# MCU.net
KiCad netlist of a schematic drawn in Altium Designer
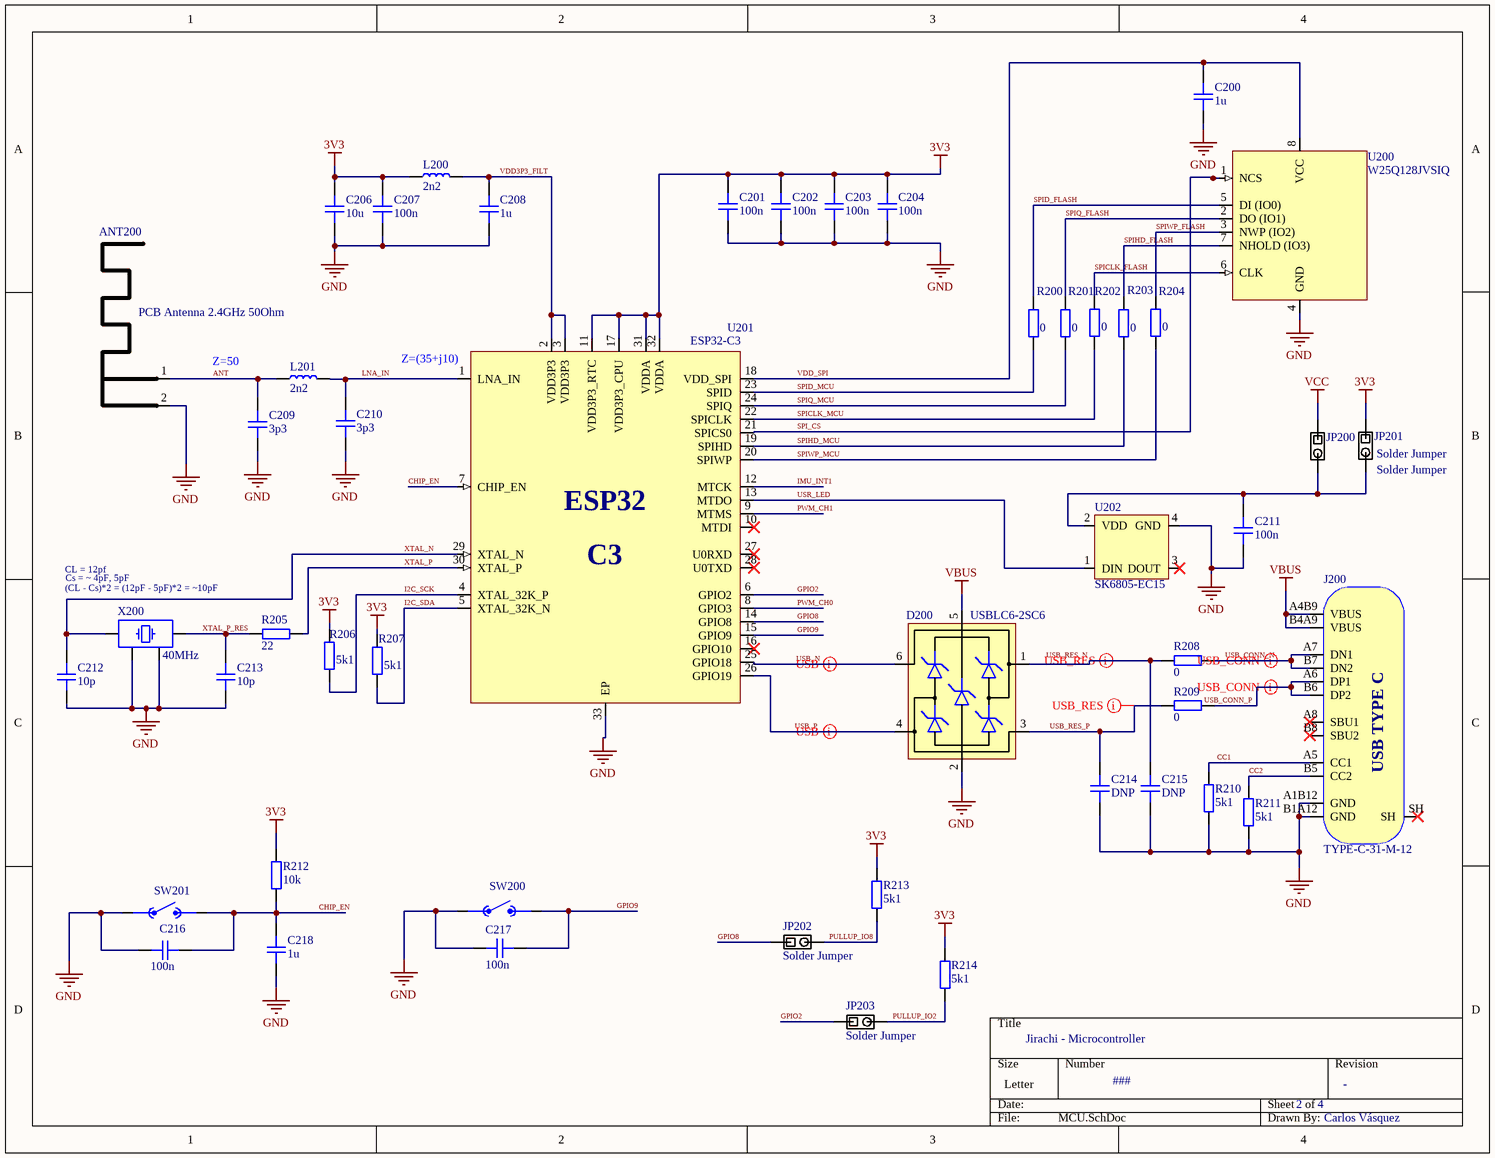
[diagram p0: MCU.SchDoc]

(export (version "E")
  (design (tool "Eeschema 10.0.6"))
  (components
    (comp (ref "ANT200")
      (value "PCB Antenna 2.4GHz 50Ohm")
      (footprint "ANT_IFA_USB_2_4GHZ_50R")
      (description "Inverted F 2.4GHz ISM PCB Antenna 50 Ohm")
      (libsource (lib "Schematic-Lib-PhilsLab") (part "ANT_IFA_USB_2_4GHZ_50R"))
    )
    (comp (ref "C200")
      (value "1u")
      (footprint "CAP_0402")
      (description "Capacitor SMD 0402")
      (libsource (lib "Schematic-Lib-PhilsLab") (part "CAP_0402"))
    )
    (comp (ref "C201")
      (value "100n")
      (footprint "CAP_0402")
      (description "Capacitor SMD 0402")
      (libsource (lib "Schematic-Lib-PhilsLab") (part "CAP_0402"))
    )
    (comp (ref "C202")
      (value "100n")
      (footprint "CAP_0402")
      (description "Capacitor SMD 0402")
      (libsource (lib "Schematic-Lib-PhilsLab") (part "CAP_0402"))
    )
    (comp (ref "C203")
      (value "100n")
      (footprint "CAP_0402")
      (description "Capacitor SMD 0402")
      (libsource (lib "Schematic-Lib-PhilsLab") (part "CAP_0402"))
    )
    (comp (ref "C204")
      (value "100n")
      (footprint "CAP_0402")
      (description "Capacitor SMD 0402")
      (libsource (lib "Schematic-Lib-PhilsLab") (part "CAP_0402"))
    )
    (comp (ref "C206")
      (value "10u")
      (footprint "CAP_0603")
      (description "Capacitor SMD 0603")
      (libsource (lib "Schematic-Lib-PhilsLab") (part "CAP_0603"))
    )
    (comp (ref "C207")
      (value "100n")
      (footprint "CAP_0402")
      (description "Capacitor SMD 0402")
      (libsource (lib "Schematic-Lib-PhilsLab") (part "CAP_0402"))
    )
    (comp (ref "C208")
      (value "1u")
      (footprint "CAP_0402")
      (description "Capacitor SMD 0402")
      (libsource (lib "Schematic-Lib-PhilsLab") (part "CAP_0402"))
    )
    (comp (ref "C209")
      (value "3p3")
      (footprint "CAP_0402")
      (description "Capacitor SMD 0402")
      (libsource (lib "Schematic-Lib-PhilsLab") (part "CAP_0402"))
    )
    (comp (ref "C210")
      (value "3p3")
      (footprint "CAP_0402")
      (description "Capacitor SMD 0402")
      (libsource (lib "Schematic-Lib-PhilsLab") (part "CAP_0402"))
    )
    (comp (ref "C211")
      (value "100n")
      (footprint "CAP_0402")
      (description "Capacitor SMD 0402")
      (libsource (lib "Schematic-Lib-PhilsLab") (part "CAP_0402"))
    )
    (comp (ref "C212")
      (value "10p")
      (footprint "CAP_0402")
      (description "Capacitor SMD 0402")
      (libsource (lib "Schematic-Lib-PhilsLab") (part "CAP_0402"))
    )
    (comp (ref "C213")
      (value "10p")
      (footprint "CAP_0402")
      (description "Capacitor SMD 0402")
      (libsource (lib "Schematic-Lib-PhilsLab") (part "CAP_0402"))
    )
    (comp (ref "C214")
      (value "DNP")
      (footprint "CAP_0603")
      (description "Capacitor SMD 0603")
      (libsource (lib "Schematic-Lib-PhilsLab") (part "CAP_0603"))
    )
    (comp (ref "C215")
      (value "DNP")
      (footprint "CAP_0603")
      (description "Capacitor SMD 0603")
      (libsource (lib "Schematic-Lib-PhilsLab") (part "CAP_0603"))
    )
    (comp (ref "C216")
      (value "100n")
      (footprint "CAP_0402")
      (description "Capacitor SMD 0402")
      (libsource (lib "Schematic-Lib-PhilsLab") (part "CAP_0402"))
    )
    (comp (ref "C217")
      (value "100n")
      (footprint "CAP_0402")
      (description "Capacitor SMD 0402")
      (libsource (lib "Schematic-Lib-PhilsLab") (part "CAP_0402"))
    )
    (comp (ref "C218")
      (value "1u")
      (footprint "CAP_0402")
      (description "Capacitor SMD 0402")
      (libsource (lib "Schematic-Lib-PhilsLab") (part "CAP_0402"))
    )
    (comp (ref "D200")
      (value "USBLC6-2SC6")
      (footprint "SOT-23-6")
      (description "Low-Capacitance ESD Protection USB")
      (fields (field (name "MANUFACTURER") "STMicroelectronics"))
      (libsource (lib "Schematic-Lib-PhilsLab") (part "USBLC6-2SC6"))
    )
    (comp (ref "J200")
      (value "TYPE-C-31-M-12")
      (footprint "TYPE-C-31-M-12")
      (description "USB Type C Connector Horizontal SMT")
      (fields (field (name "MANUFACTURER") "Koren Hroparts"))
      (libsource (lib "Schematic-Lib-PhilsLab") (part "TYPE-C-31-M-12"))
    )
    (comp (ref "JP200")
      (value "Solder Jumper")
      (footprint "SolderJumper_Single")
      (description "Solder Jumper Single 0.5mm Pitch")
      (libsource (lib "Schematic-Lib-PhilsLab") (part "SolderJumper_Single"))
    )
    (comp (ref "JP201")
      (value "Solder Jumper")
      (footprint "SolderJumper_Single")
      (description "Solder Jumper Single 0.5mm Pitch")
      (libsource (lib "Schematic-Lib-PhilsLab") (part "SolderJumper_Single"))
    )
    (comp (ref "JP202")
      (value "Solder Jumper")
      (footprint "SolderJumper_Single")
      (description "Solder Jumper Single 0.5mm Pitch")
      (libsource (lib "Schematic-Lib-PhilsLab") (part "SolderJumper_Single"))
    )
    (comp (ref "JP203")
      (value "Solder Jumper")
      (footprint "SolderJumper_Single")
      (description "Solder Jumper Single 0.5mm Pitch")
      (libsource (lib "Schematic-Lib-PhilsLab") (part "SolderJumper_Single"))
    )
    (comp (ref "L200")
      (value "2n2")
      (footprint "IND_0402")
      (description "Inductor SMD 0402")
      (libsource (lib "Schematic-Lib-PhilsLab") (part "IND_0402"))
    )
    (comp (ref "L201")
      (value "2n2")
      (footprint "IND_0402")
      (description "Inductor SMD 0402")
      (libsource (lib "Schematic-Lib-PhilsLab") (part "IND_0402"))
    )
    (comp (ref "R200")
      (value "0")
      (footprint "RES_0402")
      (description "Resistor SMD 0402")
      (libsource (lib "Schematic-Lib-PhilsLab") (part "RES_0402"))
    )
    (comp (ref "R201")
      (value "0")
      (footprint "RES_0402")
      (description "Resistor SMD 0402")
      (libsource (lib "Schematic-Lib-PhilsLab") (part "RES_0402"))
    )
    (comp (ref "R202")
      (value "0")
      (footprint "RES_0402")
      (description "Resistor SMD 0402")
      (libsource (lib "Schematic-Lib-PhilsLab") (part "RES_0402"))
    )
    (comp (ref "R203")
      (value "0")
      (footprint "RES_0402")
      (description "Resistor SMD 0402")
      (libsource (lib "Schematic-Lib-PhilsLab") (part "RES_0402"))
    )
    (comp (ref "R204")
      (value "0")
      (footprint "RES_0402")
      (description "Resistor SMD 0402")
      (libsource (lib "Schematic-Lib-PhilsLab") (part "RES_0402"))
    )
    (comp (ref "R205")
      (value "22")
      (footprint "RES_0402")
      (description "Resistor SMD 0402")
      (libsource (lib "Schematic-Lib-PhilsLab") (part "RES_0402"))
    )
    (comp (ref "R206")
      (value "5k1")
      (footprint "RES_0402")
      (description "Resistor SMD 0402")
      (libsource (lib "Schematic-Lib-PhilsLab") (part "RES_0402"))
    )
    (comp (ref "R207")
      (value "5k1")
      (footprint "RES_0402")
      (description "Resistor SMD 0402")
      (libsource (lib "Schematic-Lib-PhilsLab") (part "RES_0402"))
    )
    (comp (ref "R208")
      (value "0")
      (footprint "RES_0402")
      (description "Resistor SMD 0402")
      (libsource (lib "Schematic-Lib-PhilsLab") (part "RES_0402"))
    )
    (comp (ref "R209")
      (value "0")
      (footprint "RES_0402")
      (description "Resistor SMD 0402")
      (libsource (lib "Schematic-Lib-PhilsLab") (part "RES_0402"))
    )
    (comp (ref "R210")
      (value "5k1")
      (footprint "RES_0402")
      (description "Resistor SMD 0402")
      (libsource (lib "Schematic-Lib-PhilsLab") (part "RES_0402"))
    )
    (comp (ref "R211")
      (value "5k1")
      (footprint "RES_0402")
      (description "Resistor SMD 0402")
      (libsource (lib "Schematic-Lib-PhilsLab") (part "RES_0402"))
    )
    (comp (ref "R212")
      (value "10k")
      (footprint "RES_0402")
      (description "Resistor SMD 0402")
      (libsource (lib "Schematic-Lib-PhilsLab") (part "RES_0402"))
    )
    (comp (ref "R213")
      (value "5k1")
      (footprint "RES_0402")
      (description "Resistor SMD 0402")
      (libsource (lib "Schematic-Lib-PhilsLab") (part "RES_0402"))
    )
    (comp (ref "R214")
      (value "5k1")
      (footprint "RES_0402")
      (description "Resistor SMD 0402")
      (libsource (lib "Schematic-Lib-PhilsLab") (part "RES_0402"))
    )
    (comp (ref "SW200")
      (value "SW SPST SMD Terreneitor")
      (footprint "SW SPST SMD Terreneitor")
      (description "SPST SW TS-1187A-B-A-B")
      (libsource (lib "TerreneitorLib") (part "SW SPST SMD Terreneitor"))
    )
    (comp (ref "SW201")
      (value "SW SPST SMD Terreneitor")
      (footprint "SW SPST SMD Terreneitor")
      (description "SPST SW TS-1187A-B-A-B")
      (libsource (lib "TerreneitorLib") (part "SW SPST SMD Terreneitor"))
    )
    (comp (ref "U200")
      (value "W25Q128JVSIQ")
      (footprint "SOIC8_208 mil")
      (description "128M-BIT\r\nSERIAL FLASH MEMORY WITH\r\nDUAL/QUAD SPI & QPI & DTR SOIC-8 208 MIL")
      (fields
        (field (name "MANUFACTURER") "Winbond")
        (field (name "MANUFACTURER PART NUMBER") "W25Q128JVSIM")
      )
      (libsource (lib "Schematic-Lib-PhilsLab") (part "W25Q128JVSIQ"))
    )
    (comp (ref "U201")
      (value "ESP32-C3")
      (footprint "QFN32-5x5")
      (fields (field (name "MANUFACTURER") "Espressif"))
      (libsource (lib "Schematic-Lib-PhilsLab") (part "ESP32-C3"))
    )
    (comp (ref "U202")
      (value "SK6805-EC15")
      (footprint "SK6805-EC15")
      (libsource (lib "TerreneitorLib") (part "SK6805-EC15"))
    )
    (comp (ref "X200")
      (value "40MHz")
      (footprint "XTAL_3225")
      (description "Crystal SMD 40MHz 10PPM 12pF 3225")
      (fields
        (field (name "MANUFACTURER") "Epson")
        (field (name "MANUFACTURER PART NUMBER") "TSX-3225 24.0000MF15X-AC")
      )
      (libsource (lib "Schematic-Lib-PhilsLab") (part "TSX-3225_24.0000MF15X-AC"))
    )
  )
  (nets
    (net (code "1") (name "/ANT") (class "Default")
      (node (ref "ANT200") (pin "1") (pinfunction "RF_1") (pintype "passive"))
      (node (ref "C209") (pin "2") (pinfunction "2_2") (pintype "passive"))
      (node (ref "L201") (pin "1") (pinfunction "1_1") (pintype "passive"))
    )
    (net (code "2") (name "/CC1") (class "Default")
      (node (ref "J200") (pin "A5") (pinfunction "CC1_A5") (pintype "passive"))
      (node (ref "R210") (pin "2") (pinfunction "2_2") (pintype "passive"))
    )
    (net (code "3") (name "/CC2") (class "Default")
      (node (ref "J200") (pin "B5") (pinfunction "CC2_B5") (pintype "tri_state"))
      (node (ref "R211") (pin "2") (pinfunction "2_2") (pintype "passive"))
    )
    (net (code "4") (name "/CHIP_EN") (class "Default")
      (node (ref "C216") (pin "1") (pinfunction "1_1") (pintype "passive"))
      (node (ref "C218") (pin "2") (pinfunction "2_2") (pintype "passive"))
      (node (ref "R212") (pin "1") (pinfunction "1_1") (pintype "passive"))
      (node (ref "SW201") (pin "2") (pinfunction "2_2") (pintype "passive"))
      (node (ref "U201") (pin "7") (pinfunction "CHIP_EN_7") (pintype "input"))
    )
    (net (code "5") (name "/GPIO2") (class "Default")
      (node (ref "JP203") (pin "1") (pinfunction "1_1") (pintype "passive"))
      (node (ref "U201") (pin "6") (pinfunction "GPIO2_6") (pintype "bidirectional"))
    )
    (net (code "6") (name "/GPIO8") (class "Default")
      (node (ref "JP202") (pin "1") (pinfunction "1_1") (pintype "passive"))
      (node (ref "U201") (pin "14") (pinfunction "GPIO8_14") (pintype "bidirectional"))
    )
    (net (code "7") (name "/GPIO9") (class "Default")
      (node (ref "C217") (pin "1") (pinfunction "1_1") (pintype "passive"))
      (node (ref "SW200") (pin "2") (pinfunction "2_2") (pintype "passive"))
      (node (ref "U201") (pin "15") (pinfunction "GPIO9_15") (pintype "bidirectional"))
    )
    (net (code "8") (name "/I2C_SCK") (class "Default")
      (node (ref "R206") (pin "1") (pinfunction "1_1") (pintype "passive"))
      (node (ref "U201") (pin "4") (pinfunction "XTAL_32K_P_4") (pintype "bidirectional"))
    )
    (net (code "9") (name "/I2C_SDA") (class "Default")
      (node (ref "R207") (pin "1") (pinfunction "1_1") (pintype "passive"))
      (node (ref "U201") (pin "5") (pinfunction "XTAL_32K_N_5") (pintype "bidirectional"))
    )
    (net (code "10") (name "/IMU_INT1") (class "Default")
      (node (ref "U201") (pin "12") (pinfunction "MTCK_12") (pintype "bidirectional"))
    )
    (net (code "11") (name "/LNA_IN") (class "Default")
      (node (ref "C210") (pin "2") (pinfunction "2_2") (pintype "passive"))
      (node (ref "L201") (pin "2") (pinfunction "2_2") (pintype "passive"))
      (node (ref "U201") (pin "1") (pinfunction "LNA_IN_1") (pintype "bidirectional"))
    )
    (net (code "12") (name "/PULLUP_IO2") (class "Default")
      (node (ref "JP203") (pin "2") (pinfunction "2_2") (pintype "passive"))
      (node (ref "R214") (pin "1") (pinfunction "1_1") (pintype "passive"))
    )
    (net (code "13") (name "/PULLUP_IO8") (class "Default")
      (node (ref "JP202") (pin "2") (pinfunction "2_2") (pintype "passive"))
      (node (ref "R213") (pin "1") (pinfunction "1_1") (pintype "passive"))
    )
    (net (code "14") (name "/PWM_CH0") (class "Default")
      (node (ref "U201") (pin "8") (pinfunction "GPIO3_8") (pintype "bidirectional"))
    )
    (net (code "15") (name "/PWM_CH1") (class "Default")
      (node (ref "U201") (pin "9") (pinfunction "MTMS_9") (pintype "bidirectional"))
    )
    (net (code "16") (name "/SPICLK_FLASH") (class "Default")
      (node (ref "R202") (pin "2") (pinfunction "2_2") (pintype "passive"))
      (node (ref "U200") (pin "6") (pinfunction "CLK_6") (pintype "input"))
    )
    (net (code "17") (name "/SPICLK_MCU") (class "Default")
      (node (ref "R202") (pin "1") (pinfunction "1_1") (pintype "passive"))
      (node (ref "U201") (pin "22") (pinfunction "SPICLK_22") (pintype "bidirectional"))
    )
    (net (code "18") (name "/SPID_FLASH") (class "Default")
      (node (ref "R200") (pin "2") (pinfunction "2_2") (pintype "passive"))
      (node (ref "U200") (pin "5") (pinfunction "DI_(IO0)_5") (pintype "bidirectional"))
    )
    (net (code "19") (name "/SPID_MCU") (class "Default")
      (node (ref "R200") (pin "1") (pinfunction "1_1") (pintype "passive"))
      (node (ref "U201") (pin "23") (pinfunction "SPID_23") (pintype "bidirectional"))
    )
    (net (code "20") (name "/SPIHD_FLASH") (class "Default")
      (node (ref "R203") (pin "2") (pinfunction "2_2") (pintype "passive"))
      (node (ref "U200") (pin "7") (pinfunction "NHOLD_(IO3)_7") (pintype "bidirectional"))
    )
    (net (code "21") (name "/SPIHD_MCU") (class "Default")
      (node (ref "R203") (pin "1") (pinfunction "1_1") (pintype "passive"))
      (node (ref "U201") (pin "19") (pinfunction "SPIHD_19") (pintype "bidirectional"))
    )
    (net (code "22") (name "/SPIQ_FLASH") (class "Default")
      (node (ref "R201") (pin "2") (pinfunction "2_2") (pintype "passive"))
      (node (ref "U200") (pin "2") (pinfunction "DO_(IO1)_2") (pintype "bidirectional"))
    )
    (net (code "23") (name "/SPIQ_MCU") (class "Default")
      (node (ref "R201") (pin "1") (pinfunction "1_1") (pintype "passive"))
      (node (ref "U201") (pin "24") (pinfunction "SPIQ_24") (pintype "bidirectional"))
    )
    (net (code "24") (name "/SPIWP_FLASH") (class "Default")
      (node (ref "R204") (pin "2") (pinfunction "2_2") (pintype "passive"))
      (node (ref "U200") (pin "3") (pinfunction "NWP_(IO2)_3") (pintype "bidirectional"))
    )
    (net (code "25") (name "/SPIWP_MCU") (class "Default")
      (node (ref "R204") (pin "1") (pinfunction "1_1") (pintype "passive"))
      (node (ref "U201") (pin "20") (pinfunction "SPIWP_20") (pintype "bidirectional"))
    )
    (net (code "26") (name "/SPI_CS") (class "Default")
      (node (ref "U200") (pin "1") (pinfunction "NCS_1") (pintype "input"))
      (node (ref "U201") (pin "21") (pinfunction "SPICS0_21") (pintype "bidirectional"))
    )
    (net (code "27") (name "/USB_CONN_N") (class "Default")
      (node (ref "J200") (pin "A7") (pinfunction "DN1_A7") (pintype "bidirectional"))
      (node (ref "J200") (pin "B7") (pinfunction "DN2_B7") (pintype "bidirectional"))
      (node (ref "R208") (pin "2") (pinfunction "2_2") (pintype "passive"))
    )
    (net (code "28") (name "/USB_CONN_P") (class "Default")
      (node (ref "J200") (pin "A6") (pinfunction "DP1_A6") (pintype "bidirectional"))
      (node (ref "J200") (pin "B6") (pinfunction "DP2_B6") (pintype "bidirectional"))
      (node (ref "R209") (pin "2") (pinfunction "2_2") (pintype "passive"))
    )
    (net (code "29") (name "/USB_N") (class "Default")
      (node (ref "D200") (pin "6") (pinfunction "IO1_6") (pintype "bidirectional"))
      (node (ref "U201") (pin "25") (pinfunction "GPIO18_25") (pintype "bidirectional"))
    )
    (net (code "30") (name "/USB_P") (class "Default")
      (node (ref "D200") (pin "4") (pinfunction "IO2_4") (pintype "bidirectional"))
      (node (ref "U201") (pin "26") (pinfunction "GPIO19_26") (pintype "bidirectional"))
    )
    (net (code "31") (name "/USB_RES_N") (class "Default")
      (node (ref "C215") (pin "2") (pinfunction "2_2") (pintype "passive"))
      (node (ref "D200") (pin "1") (pinfunction "IO1_1") (pintype "bidirectional"))
      (node (ref "R208") (pin "1") (pinfunction "1_1") (pintype "passive"))
    )
    (net (code "32") (name "/USB_RES_P") (class "Default")
      (node (ref "C214") (pin "2") (pinfunction "2_2") (pintype "passive"))
      (node (ref "D200") (pin "3") (pinfunction "IO2_3") (pintype "bidirectional"))
      (node (ref "R209") (pin "1") (pinfunction "1_1") (pintype "passive"))
    )
    (net (code "33") (name "/USR_LED") (class "Default")
      (node (ref "U201") (pin "13") (pinfunction "MTDO_13") (pintype "bidirectional"))
      (node (ref "U202") (pin "1") (pinfunction "DIN_1") (pintype "passive"))
    )
    (net (code "34") (name "/VDD3P3_FILT") (class "Default")
      (node (ref "C208") (pin "2") (pinfunction "2_2") (pintype "passive"))
      (node (ref "L200") (pin "2") (pinfunction "2_2") (pintype "passive"))
      (node (ref "U201") (pin "2") (pinfunction "VDD3P3_2") (pintype "power_in"))
      (node (ref "U201") (pin "3") (pinfunction "VDD3P3_3") (pintype "power_in"))
    )
    (net (code "35") (name "/VDD_SPI") (class "Default")
      (node (ref "C200") (pin "2") (pinfunction "2_2") (pintype "passive"))
      (node (ref "U200") (pin "8") (pinfunction "VCC_8") (pintype "power_in"))
      (node (ref "U201") (pin "18") (pinfunction "VDD_SPI_18") (pintype "power_in"))
    )
    (net (code "36") (name "/XTAL_N") (class "Default")
      (node (ref "C212") (pin "1") (pinfunction "1_1") (pintype "passive"))
      (node (ref "U201") (pin "29") (pinfunction "XTAL_N_29") (pintype "input"))
      (node (ref "X200") (pin "1") (pinfunction "1_1") (pintype "passive"))
    )
    (net (code "37") (name "/XTAL_P") (class "Default")
      (node (ref "R205") (pin "2") (pinfunction "2_2") (pintype "passive"))
      (node (ref "U201") (pin "30") (pinfunction "XTAL_P_30") (pintype "input"))
    )
    (net (code "38") (name "/XTAL_P_RES") (class "Default")
      (node (ref "C213") (pin "1") (pinfunction "1_1") (pintype "passive"))
      (node (ref "R205") (pin "1") (pinfunction "1_1") (pintype "passive"))
      (node (ref "X200") (pin "3") (pinfunction "3_3") (pintype "passive"))
    )
    (net (code "39") (name "3V3") (class "Default")
      (node (ref "C201") (pin "1") (pinfunction "1_1") (pintype "passive"))
      (node (ref "C202") (pin "1") (pinfunction "1_1") (pintype "passive"))
      (node (ref "C203") (pin "1") (pinfunction "1_1") (pintype "passive"))
      (node (ref "C204") (pin "1") (pinfunction "1_1") (pintype "passive"))
      (node (ref "C206") (pin "1") (pinfunction "1_1") (pintype "passive"))
      (node (ref "C207") (pin "1") (pinfunction "1_1") (pintype "passive"))
      (node (ref "JP201") (pin "1") (pinfunction "1_1") (pintype "passive"))
      (node (ref "L200") (pin "1") (pinfunction "1_1") (pintype "passive"))
      (node (ref "R206") (pin "2") (pinfunction "2_2") (pintype "passive"))
      (node (ref "R207") (pin "2") (pinfunction "2_2") (pintype "passive"))
      (node (ref "R212") (pin "2") (pinfunction "2_2") (pintype "passive"))
      (node (ref "R213") (pin "2") (pinfunction "2_2") (pintype "passive"))
      (node (ref "R214") (pin "2") (pinfunction "2_2") (pintype "passive"))
      (node (ref "U201") (pin "11") (pinfunction "VDD3P3_RTC_11") (pintype "power_in"))
      (node (ref "U201") (pin "17") (pinfunction "VDD3P3_CPU_17") (pintype "power_in"))
      (node (ref "U201") (pin "31") (pinfunction "VDDA_31") (pintype "power_in"))
      (node (ref "U201") (pin "32") (pinfunction "VDDA_32") (pintype "power_in"))
    )
    (net (code "40") (name "GND") (class "Default")
      (node (ref "ANT200") (pin "2") (pinfunction "GND_2") (pintype "passive"))
      (node (ref "C200") (pin "1") (pinfunction "1_1") (pintype "passive"))
      (node (ref "C201") (pin "2") (pinfunction "2_2") (pintype "passive"))
      (node (ref "C202") (pin "2") (pinfunction "2_2") (pintype "passive"))
      (node (ref "C203") (pin "2") (pinfunction "2_2") (pintype "passive"))
      (node (ref "C204") (pin "2") (pinfunction "2_2") (pintype "passive"))
      (node (ref "C206") (pin "2") (pinfunction "2_2") (pintype "passive"))
      (node (ref "C207") (pin "2") (pinfunction "2_2") (pintype "passive"))
      (node (ref "C208") (pin "1") (pinfunction "1_1") (pintype "passive"))
      (node (ref "C209") (pin "1") (pinfunction "1_1") (pintype "passive"))
      (node (ref "C210") (pin "1") (pinfunction "1_1") (pintype "passive"))
      (node (ref "C211") (pin "1") (pinfunction "1_1") (pintype "passive"))
      (node (ref "C212") (pin "2") (pinfunction "2_2") (pintype "passive"))
      (node (ref "C213") (pin "2") (pinfunction "2_2") (pintype "passive"))
      (node (ref "C214") (pin "1") (pinfunction "1_1") (pintype "passive"))
      (node (ref "C215") (pin "1") (pinfunction "1_1") (pintype "passive"))
      (node (ref "C216") (pin "2") (pinfunction "2_2") (pintype "passive"))
      (node (ref "C217") (pin "2") (pinfunction "2_2") (pintype "passive"))
      (node (ref "C218") (pin "1") (pinfunction "1_1") (pintype "passive"))
      (node (ref "D200") (pin "2") (pinfunction "GND_2") (pintype "power_in"))
      (node (ref "J200") (pin "A1B12") (pinfunction "GND_A1B12") (pintype "power_in"))
      (node (ref "J200") (pin "B1A12") (pinfunction "GND_B1A12") (pintype "power_in"))
      (node (ref "R210") (pin "1") (pinfunction "1_1") (pintype "passive"))
      (node (ref "R211") (pin "1") (pinfunction "1_1") (pintype "passive"))
      (node (ref "SW200") (pin "1") (pinfunction "1_1") (pintype "passive"))
      (node (ref "SW201") (pin "1") (pinfunction "1_1") (pintype "passive"))
      (node (ref "U200") (pin "4") (pinfunction "GND_4") (pintype "power_in"))
      (node (ref "U201") (pin "33") (pinfunction "EP_33") (pintype "power_in"))
      (node (ref "U202") (pin "4") (pinfunction "GND_4") (pintype "passive"))
      (node (ref "X200") (pin "2") (pinfunction "2_2") (pintype "passive"))
      (node (ref "X200") (pin "4") (pinfunction "4_4") (pintype "passive"))
    )
    (net (code "41") (name "Net-(U202-VDD)") (class "Default")
      (node (ref "C211") (pin "2") (pinfunction "2_2") (pintype "passive"))
      (node (ref "JP200") (pin "2") (pinfunction "2_2") (pintype "passive"))
      (node (ref "JP201") (pin "2") (pinfunction "2_2") (pintype "passive"))
      (node (ref "U202") (pin "2") (pinfunction "VDD_2") (pintype "passive"))
    )
    (net (code "42") (name "VBUS") (class "Default")
      (node (ref "D200") (pin "5") (pinfunction "VBUS_5") (pintype "power_in"))
      (node (ref "J200") (pin "A4B9") (pinfunction "VBUS_A4B9") (pintype "power_in"))
      (node (ref "J200") (pin "B4A9") (pinfunction "VBUS_B4A9") (pintype "power_in"))
    )
    (net (code "43") (name "VCC") (class "Default")
      (node (ref "JP200") (pin "1") (pinfunction "1_1") (pintype "passive"))
    )
    (net (code "44") (name "unconnected-(J200-PadSH)") (class "Default")
      (node (ref "J200") (pin "SH") (pinfunction "SH_SH") (pintype "power_in+no_connect"))
    )
    (net (code "45") (name "unconnected-(J200-SBU1-PadA8)") (class "Default")
      (node (ref "J200") (pin "A8") (pinfunction "SBU1_A8") (pintype "bidirectional+no_connect"))
    )
    (net (code "46") (name "unconnected-(J200-SBU2-PadB8)") (class "Default")
      (node (ref "J200") (pin "B8") (pinfunction "SBU2_B8") (pintype "bidirectional+no_connect"))
    )
    (net (code "47") (name "unconnected-(U201-GPIO10-Pad16)") (class "Default")
      (node (ref "U201") (pin "16") (pinfunction "GPIO10_16") (pintype "bidirectional+no_connect"))
    )
    (net (code "48") (name "unconnected-(U201-MTDI-Pad10)") (class "Default")
      (node (ref "U201") (pin "10") (pinfunction "MTDI_10") (pintype "bidirectional+no_connect"))
    )
    (net (code "49") (name "unconnected-(U201-U0RXD-Pad27)") (class "Default")
      (node (ref "U201") (pin "27") (pinfunction "U0RXD_27") (pintype "bidirectional+no_connect"))
    )
    (net (code "50") (name "unconnected-(U201-U0TXD-Pad28)") (class "Default")
      (node (ref "U201") (pin "28") (pinfunction "U0TXD_28") (pintype "bidirectional+no_connect"))
    )
    (net (code "51") (name "unconnected-(U202-DOUT-Pad3)") (class "Default")
      (node (ref "U202") (pin "3") (pinfunction "DOUT_3") (pintype "passive+no_connect"))
    )
  )
)
